# STM32_MACH3-Interfaceboard_V2.net
KiCad netlist of a schematic drawn in EAGLE
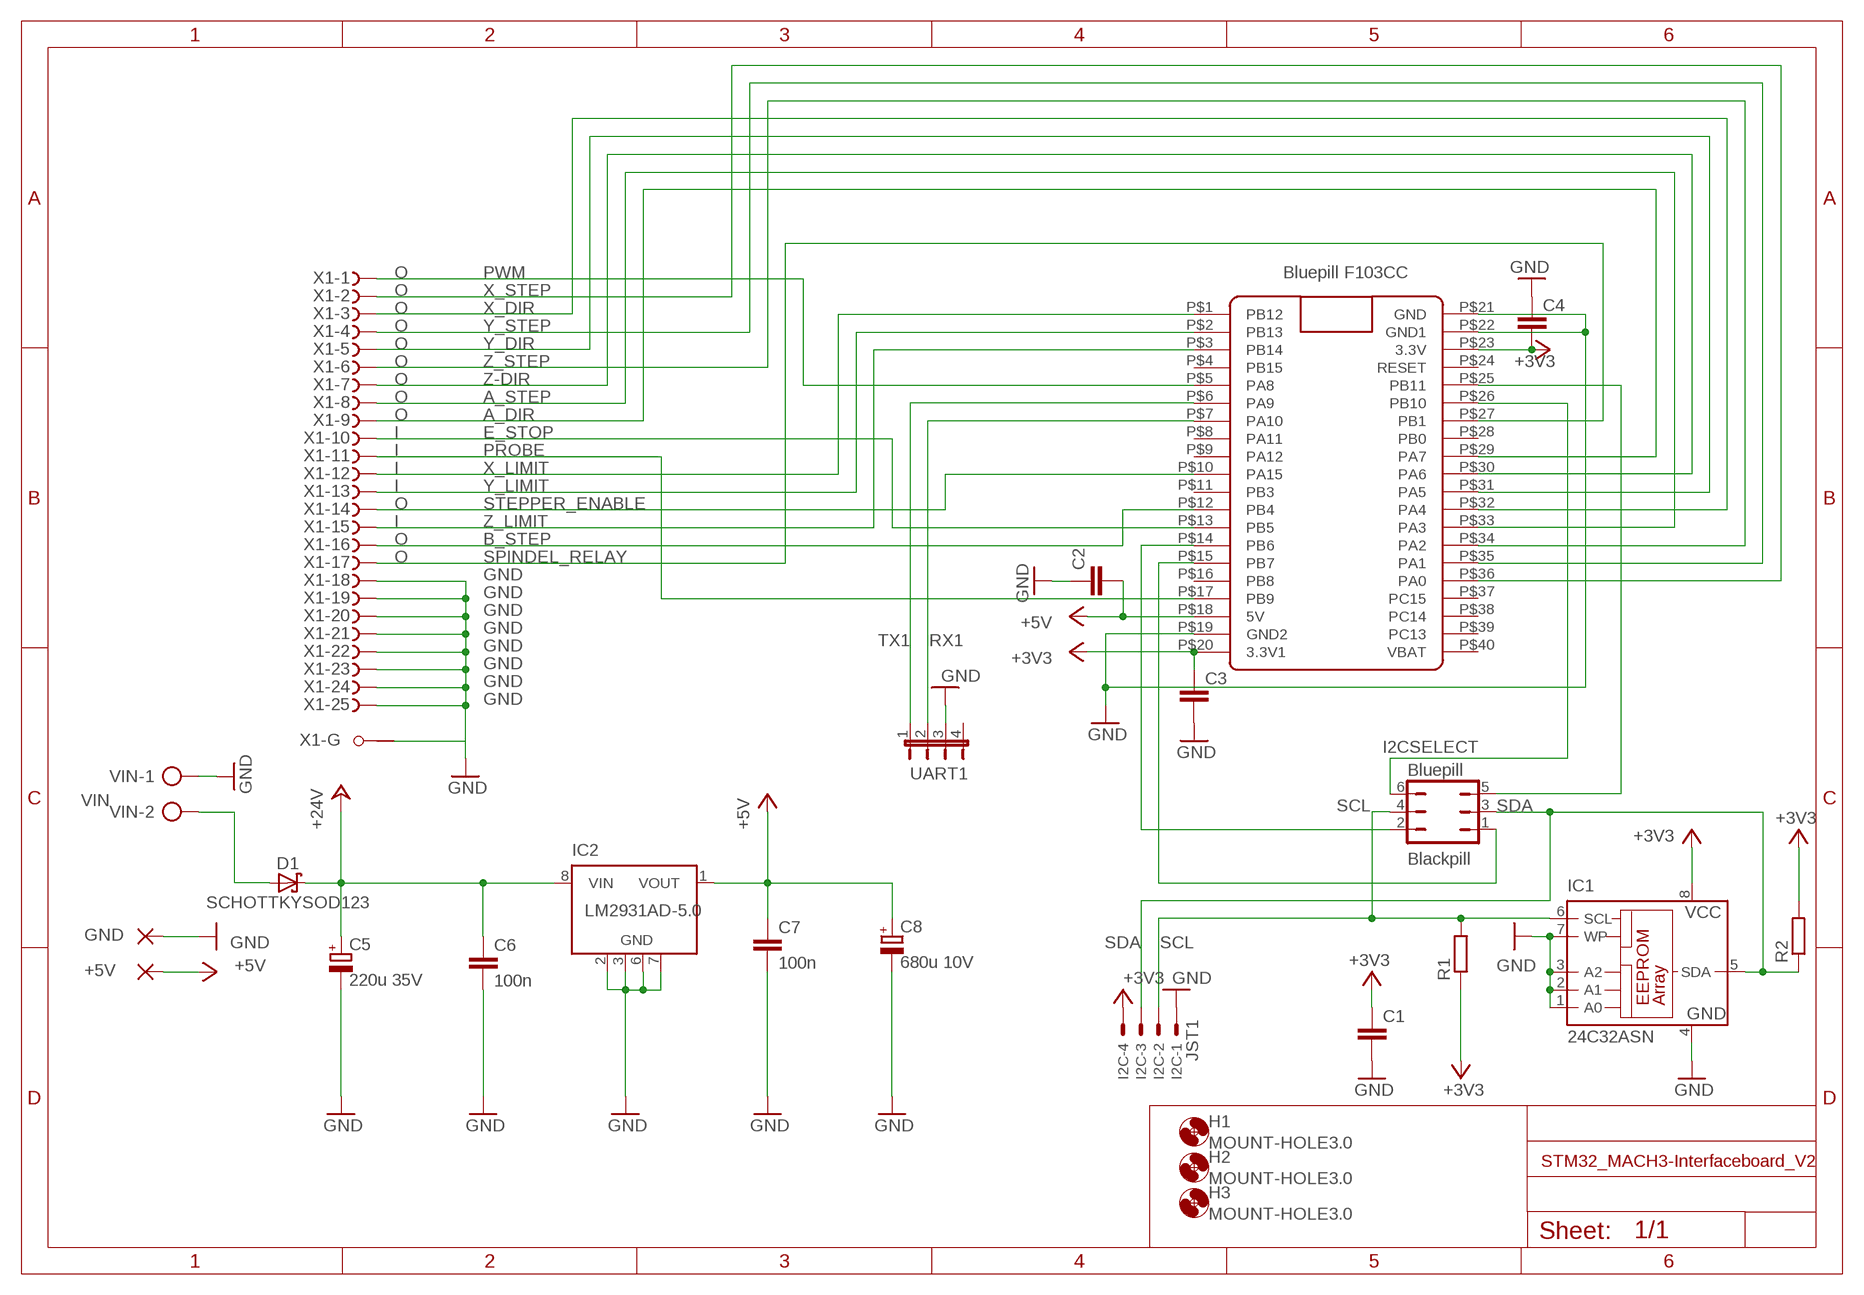
[diagram p0: schematic, sheet 1]

(export (version "E")
  (design (tool "Eeschema 10.0.6"))
  (components
    (comp (ref "+5V")
      (value "2,54/1,0")
      (footprint "eagle-import:2,54_1,0")
      (libsource (lib "eagle-import") (part "2,54/1,0"))
    )
    (comp (ref "C1")
      (value "C-EUC0805")
      (footprint "eagle-import:C0805")
      (libsource (lib "eagle-import") (part "C-EUC0805"))
    )
    (comp (ref "C2")
      (value "C-EUC0805")
      (footprint "eagle-import:C0805")
      (libsource (lib "eagle-import") (part "C-EUC0805"))
    )
    (comp (ref "C3")
      (value "C-EUC0805")
      (footprint "eagle-import:C0805")
      (libsource (lib "eagle-import") (part "C-EUC0805"))
    )
    (comp (ref "C4")
      (value "C-EUC0805")
      (footprint "eagle-import:C0805")
      (libsource (lib "eagle-import") (part "C-EUC0805"))
    )
    (comp (ref "C5")
      (value "220u 35V")
      (footprint "eagle-import:PANASONIC_E7")
      (libsource (lib "eagle-import") (part "C_POLARIZEDE7"))
    )
    (comp (ref "C6")
      (value "100n")
      (footprint "eagle-import:C0805")
      (libsource (lib "eagle-import") (part "CC0805"))
    )
    (comp (ref "C7")
      (value "100n")
      (footprint "eagle-import:C0805")
      (libsource (lib "eagle-import") (part "CC0805"))
    )
    (comp (ref "C8")
      (value "680u 10V")
      (footprint "eagle-import:PANASONIC_E7")
      (libsource (lib "eagle-import") (part "C_POLARIZEDE7"))
    )
    (comp (ref "D1")
      (value "SCHOTTKYSOD123")
      (footprint "eagle-import:SOD123")
      (libsource (lib "eagle-import") (part "SCHOTTKYSOD123"))
    )
    (comp (ref "GND")
      (value "2,54/1,0")
      (footprint "eagle-import:2,54_1,0")
      (libsource (lib "eagle-import") (part "2,54/1,0"))
    )
    (comp (ref "H1")
      (value "MOUNT-HOLE3.0")
      (footprint "eagle-import:3,0")
      (libsource (lib "eagle-import") (part "MOUNT-HOLE3.0"))
    )
    (comp (ref "H2")
      (value "MOUNT-HOLE3.0")
      (footprint "eagle-import:3,0")
      (libsource (lib "eagle-import") (part "MOUNT-HOLE3.0"))
    )
    (comp (ref "H3")
      (value "MOUNT-HOLE3.0")
      (footprint "eagle-import:3,0")
      (libsource (lib "eagle-import") (part "MOUNT-HOLE3.0"))
    )
    (comp (ref "I2C")
      (value "JST1")
      (footprint "eagle-import:JST-XH-04-PACKAGE-LONG-PAD")
      (libsource (lib "eagle-import") (part "JST-XH-04-PIN-LONG-PAD"))
    )
    (comp (ref "I2CSELECT")
      (value "JP3Q")
      (footprint "eagle-import:JP3Q")
      (libsource (lib "eagle-import") (part "JP3Q"))
    )
    (comp (ref "IC1")
      (value "24C32ASN")
      (footprint "eagle-import:SO-08")
      (fields (field (name "MPN") "IS24C32A-2GLI"))
      (libsource (lib "eagle-import") (part "24SNC32A"))
    )
    (comp (ref "IC2")
      (value "LM2931AD-5.0")
      (footprint "eagle-import:SOIC8")
      (libsource (lib "eagle-import") (part "LM2931AD-5.0"))
    )
    (comp (ref "R1")
      (value "R-EU_R0805")
      (footprint "eagle-import:R0805")
      (libsource (lib "eagle-import") (part "R-EU_R0805"))
    )
    (comp (ref "R2")
      (value "R-EU_R0805")
      (footprint "eagle-import:R0805")
      (libsource (lib "eagle-import") (part "R-EU_R0805"))
    )
    (comp (ref "U$1")
      (value "BLUE_PILL")
      (footprint "eagle-import:BLUE_PILL")
      (libsource (lib "eagle-import") (part "BLUE_PILL"))
    )
    (comp (ref "UART1")
      (value "JP4E")
      (footprint "eagle-import:JP4")
      (libsource (lib "eagle-import") (part "JP4E"))
    )
    (comp (ref "VIN")
      (value "AK500/2")
      (footprint "eagle-import:AK500_2")
      (libsource (lib "eagle-import") (part "AK500/2"))
    )
    (comp (ref "X1")
      (value "F25HPS")
      (footprint "eagle-import:F25HP")
      (libsource (lib "eagle-import") (part "F25HPS"))
    )
  )
  (nets
    (net (code "1") (name "+3V3") (class "Default")
      (node (ref "C1") (pin "1") (pinfunction "1_1") (pintype "passive"))
      (node (ref "C3") (pin "1") (pinfunction "1_1") (pintype "passive"))
      (node (ref "C4") (pin "2") (pinfunction "2_2") (pintype "passive"))
      (node (ref "I2C") (pin "4") (pinfunction "S_4") (pintype "passive"))
      (node (ref "IC1") (pin "8") (pinfunction "VCC_8") (pintype "power_in"))
      (node (ref "R1") (pin "1") (pinfunction "1_1") (pintype "passive"))
      (node (ref "R2") (pin "2") (pinfunction "2_2") (pintype "passive"))
      (node (ref "U$1") (pin "P$20") (pinfunction "3.3V1_P$20") (pintype "bidirectional"))
      (node (ref "U$1") (pin "P$23") (pinfunction "3.3V_P$23") (pintype "bidirectional"))
    )
    (net (code "2") (name "+5V") (class "Default")
      (node (ref "+5V") (pin "1") (pinfunction "P_1") (pintype "passive"))
      (node (ref "C2") (pin "2") (pinfunction "2_2") (pintype "passive"))
      (node (ref "C7") (pin "1") (pinfunction "1_1") (pintype "passive"))
      (node (ref "C8") (pin "+") (pinfunction "+_+") (pintype "passive"))
      (node (ref "IC2") (pin "1") (pinfunction "VOUT_1") (pintype "output"))
      (node (ref "U$1") (pin "P$18") (pinfunction "5V_P$18") (pintype "bidirectional"))
    )
    (net (code "3") (name "+24V") (class "Default")
      (node (ref "C5") (pin "+") (pinfunction "+_+") (pintype "passive"))
      (node (ref "C6") (pin "1") (pinfunction "1_1") (pintype "passive"))
      (node (ref "D1") (pin "C") (pinfunction "C_C") (pintype "passive"))
      (node (ref "IC2") (pin "8") (pinfunction "VIN_8") (pintype "passive"))
    )
    (net (code "4") (name "/A_DIR") (class "Default")
      (node (ref "U$1") (pin "P$29") (pinfunction "PA7_P$29") (pintype "bidirectional"))
      (node (ref "X1") (pin "9") (pinfunction "F_9") (pintype "passive"))
    )
    (net (code "5") (name "/A_STEP") (class "Default")
      (node (ref "U$1") (pin "P$33") (pinfunction "PA3_P$33") (pintype "bidirectional"))
      (node (ref "X1") (pin "8") (pinfunction "F_8") (pintype "passive"))
    )
    (net (code "6") (name "/B_STEP") (class "Default")
      (node (ref "U$1") (pin "P$12") (pinfunction "PB4_P$12") (pintype "bidirectional"))
      (node (ref "X1") (pin "16") (pinfunction "F_16") (pintype "passive"))
    )
    (net (code "7") (name "/E_STOP") (class "Default")
      (node (ref "U$1") (pin "P$13") (pinfunction "PB5_P$13") (pintype "bidirectional"))
      (node (ref "X1") (pin "10") (pinfunction "F_10") (pintype "passive"))
    )
    (net (code "8") (name "/PROBE") (class "Default")
      (node (ref "U$1") (pin "P$17") (pinfunction "PB9_P$17") (pintype "bidirectional"))
      (node (ref "X1") (pin "11") (pinfunction "F_11") (pintype "passive"))
    )
    (net (code "9") (name "/PWM") (class "Default")
      (node (ref "U$1") (pin "P$5") (pinfunction "PA8_P$5") (pintype "bidirectional"))
      (node (ref "X1") (pin "1") (pinfunction "F_1") (pintype "passive"))
    )
    (net (code "10") (name "/RX1") (class "Default")
      (node (ref "U$1") (pin "P$7") (pinfunction "PA10_P$7") (pintype "bidirectional"))
      (node (ref "UART1") (pin "2") (pinfunction "2_2") (pintype "passive"))
    )
    (net (code "11") (name "/SCL") (class "Default")
      (node (ref "I2C") (pin "2") (pinfunction "S_2") (pintype "passive"))
      (node (ref "I2CSELECT") (pin "4") (pinfunction "4_4") (pintype "passive"))
      (node (ref "IC1") (pin "6") (pinfunction "SCL_6") (pintype "input"))
      (node (ref "R1") (pin "2") (pinfunction "2_2") (pintype "passive"))
    )
    (net (code "12") (name "/SDA") (class "Default")
      (node (ref "I2C") (pin "3") (pinfunction "S_3") (pintype "passive"))
      (node (ref "I2CSELECT") (pin "3") (pinfunction "3_3") (pintype "passive"))
      (node (ref "IC1") (pin "5") (pinfunction "SDA_5") (pintype "bidirectional"))
      (node (ref "R2") (pin "1") (pinfunction "1_1") (pintype "passive"))
    )
    (net (code "13") (name "/SPINDEL_RELAY") (class "Default")
      (node (ref "U$1") (pin "P$27") (pinfunction "PB1_P$27") (pintype "bidirectional"))
      (node (ref "X1") (pin "17") (pinfunction "F_17") (pintype "passive"))
    )
    (net (code "14") (name "/STEPPER_ENABLE") (class "Default")
      (node (ref "U$1") (pin "P$10") (pinfunction "PA15_P$10") (pintype "bidirectional"))
      (node (ref "X1") (pin "14") (pinfunction "F_14") (pintype "passive"))
    )
    (net (code "15") (name "/TX1") (class "Default")
      (node (ref "U$1") (pin "P$6") (pinfunction "PA9_P$6") (pintype "bidirectional"))
      (node (ref "UART1") (pin "1") (pinfunction "1_1") (pintype "passive"))
    )
    (net (code "16") (name "/VIN") (class "Default")
      (node (ref "D1") (pin "A") (pinfunction "A_A") (pintype "passive"))
      (node (ref "VIN") (pin "2") (pinfunction "KL_2") (pintype "passive"))
    )
    (net (code "17") (name "/X_DIR") (class "Default")
      (node (ref "U$1") (pin "P$32") (pinfunction "PA4_P$32") (pintype "bidirectional"))
      (node (ref "X1") (pin "3") (pinfunction "F_3") (pintype "passive"))
    )
    (net (code "18") (name "/X_LIMIT") (class "Default")
      (node (ref "U$1") (pin "P$1") (pinfunction "PB12_P$1") (pintype "bidirectional"))
      (node (ref "X1") (pin "12") (pinfunction "F_12") (pintype "passive"))
    )
    (net (code "19") (name "/X_STEP") (class "Default")
      (node (ref "U$1") (pin "P$36") (pinfunction "PA0_P$36") (pintype "bidirectional"))
      (node (ref "X1") (pin "2") (pinfunction "F_2") (pintype "passive"))
    )
    (net (code "20") (name "/Y_DIR") (class "Default")
      (node (ref "U$1") (pin "P$31") (pinfunction "PA5_P$31") (pintype "bidirectional"))
      (node (ref "X1") (pin "5") (pinfunction "F_5") (pintype "passive"))
    )
    (net (code "21") (name "/Y_LIMIT") (class "Default")
      (node (ref "U$1") (pin "P$2") (pinfunction "PB13_P$2") (pintype "bidirectional"))
      (node (ref "X1") (pin "13") (pinfunction "F_13") (pintype "passive"))
    )
    (net (code "22") (name "/Y_STEP") (class "Default")
      (node (ref "U$1") (pin "P$35") (pinfunction "PA1_P$35") (pintype "bidirectional"))
      (node (ref "X1") (pin "4") (pinfunction "F_4") (pintype "passive"))
    )
    (net (code "23") (name "/Z-DIR") (class "Default")
      (node (ref "U$1") (pin "P$30") (pinfunction "PA6_P$30") (pintype "bidirectional"))
      (node (ref "X1") (pin "7") (pinfunction "F_7") (pintype "passive"))
    )
    (net (code "24") (name "/Z_LIMIT") (class "Default")
      (node (ref "U$1") (pin "P$3") (pinfunction "PB14_P$3") (pintype "bidirectional"))
      (node (ref "X1") (pin "15") (pinfunction "F_15") (pintype "passive"))
    )
    (net (code "25") (name "/Z_STEP") (class "Default")
      (node (ref "U$1") (pin "P$34") (pinfunction "PA2_P$34") (pintype "bidirectional"))
      (node (ref "X1") (pin "6") (pinfunction "F_6") (pintype "passive"))
    )
    (net (code "26") (name "GND") (class "Default")
      (node (ref "C1") (pin "2") (pinfunction "2_2") (pintype "passive"))
      (node (ref "C2") (pin "1") (pinfunction "1_1") (pintype "passive"))
      (node (ref "C3") (pin "2") (pinfunction "2_2") (pintype "passive"))
      (node (ref "C4") (pin "1") (pinfunction "1_1") (pintype "passive"))
      (node (ref "C5") (pin "-") (pinfunction "-_-") (pintype "passive"))
      (node (ref "C6") (pin "2") (pinfunction "2_2") (pintype "passive"))
      (node (ref "C7") (pin "2") (pinfunction "2_2") (pintype "passive"))
      (node (ref "C8") (pin "-") (pinfunction "-_-") (pintype "passive"))
      (node (ref "GND") (pin "1") (pinfunction "P_1") (pintype "passive"))
      (node (ref "I2C") (pin "1") (pinfunction "S_1") (pintype "passive"))
      (node (ref "IC1") (pin "1") (pinfunction "A0_1") (pintype "input"))
      (node (ref "IC1") (pin "2") (pinfunction "A1_2") (pintype "input"))
      (node (ref "IC1") (pin "3") (pinfunction "A2_3") (pintype "input"))
      (node (ref "IC1") (pin "4") (pinfunction "GND_4") (pintype "power_in"))
      (node (ref "IC1") (pin "7") (pinfunction "WP_7") (pintype "input"))
      (node (ref "IC2") (pin "2") (pinfunction "GND_2") (pintype "power_in"))
      (node (ref "IC2") (pin "3") (pinfunction "GND_3") (pintype "power_in"))
      (node (ref "IC2") (pin "6") (pinfunction "GND_6") (pintype "power_in"))
      (node (ref "IC2") (pin "7") (pinfunction "GND_7") (pintype "power_in"))
      (node (ref "U$1") (pin "P$19") (pinfunction "GND2_P$19") (pintype "bidirectional"))
      (node (ref "U$1") (pin "P$21") (pinfunction "GND_P$21") (pintype "power_in"))
      (node (ref "U$1") (pin "P$22") (pinfunction "GND1_P$22") (pintype "bidirectional"))
      (node (ref "UART1") (pin "3") (pinfunction "3_3") (pintype "passive"))
      (node (ref "VIN") (pin "1") (pinfunction "KL_1") (pintype "passive"))
      (node (ref "X1") (pin "18") (pinfunction "F_18") (pintype "passive"))
      (node (ref "X1") (pin "19") (pinfunction "F_19") (pintype "passive"))
      (node (ref "X1") (pin "20") (pinfunction "F_20") (pintype "passive"))
      (node (ref "X1") (pin "21") (pinfunction "F_21") (pintype "passive"))
      (node (ref "X1") (pin "22") (pinfunction "F_22") (pintype "passive"))
      (node (ref "X1") (pin "23") (pinfunction "F_23") (pintype "passive"))
      (node (ref "X1") (pin "24") (pinfunction "F_24") (pintype "passive"))
      (node (ref "X1") (pin "25") (pinfunction "F_25") (pintype "passive"))
      (node (ref "X1") (pin "G1") (pinfunction "G1_G1") (pintype "passive"))
    )
    (net (code "27") (name "Net-(U$1-PB6)") (class "Default")
      (node (ref "I2CSELECT") (pin "2") (pinfunction "2_2") (pintype "passive"))
      (node (ref "U$1") (pin "P$14") (pinfunction "PB6_P$14") (pintype "bidirectional"))
    )
    (net (code "28") (name "Net-(U$1-PB7)") (class "Default")
      (node (ref "I2CSELECT") (pin "1") (pinfunction "1_1") (pintype "passive"))
      (node (ref "U$1") (pin "P$15") (pinfunction "PB7_P$15") (pintype "bidirectional"))
    )
    (net (code "29") (name "Net-(U$1-PB10)") (class "Default")
      (node (ref "I2CSELECT") (pin "6") (pinfunction "6_6") (pintype "passive"))
      (node (ref "U$1") (pin "P$26") (pinfunction "PB10_P$26") (pintype "bidirectional"))
    )
    (net (code "30") (name "Net-(U$1-PB11)") (class "Default")
      (node (ref "I2CSELECT") (pin "5") (pinfunction "5_5") (pintype "passive"))
      (node (ref "U$1") (pin "P$25") (pinfunction "PB11_P$25") (pintype "bidirectional"))
    )
    (net (code "31") (name "unconnected-(U$1-PA11-PadP$8)") (class "Default")
      (node (ref "U$1") (pin "P$8") (pinfunction "PA11_P$8") (pintype "bidirectional"))
    )
    (net (code "32") (name "unconnected-(U$1-PA12-PadP$9)") (class "Default")
      (node (ref "U$1") (pin "P$9") (pinfunction "PA12_P$9") (pintype "bidirectional"))
    )
    (net (code "33") (name "unconnected-(U$1-PB0-PadP$28)") (class "Default")
      (node (ref "U$1") (pin "P$28") (pinfunction "PB0_P$28") (pintype "bidirectional"))
    )
    (net (code "34") (name "unconnected-(U$1-PB3-PadP$11)") (class "Default")
      (node (ref "U$1") (pin "P$11") (pinfunction "PB3_P$11") (pintype "bidirectional"))
    )
    (net (code "35") (name "unconnected-(U$1-PB8-PadP$16)") (class "Default")
      (node (ref "U$1") (pin "P$16") (pinfunction "PB8_P$16") (pintype "bidirectional"))
    )
    (net (code "36") (name "unconnected-(U$1-PB15-PadP$4)") (class "Default")
      (node (ref "U$1") (pin "P$4") (pinfunction "PB15_P$4") (pintype "bidirectional"))
    )
    (net (code "37") (name "unconnected-(U$1-PC13-PadP$39)") (class "Default")
      (node (ref "U$1") (pin "P$39") (pinfunction "PC13_P$39") (pintype "bidirectional"))
    )
    (net (code "38") (name "unconnected-(U$1-PC14-PadP$38)") (class "Default")
      (node (ref "U$1") (pin "P$38") (pinfunction "PC14_P$38") (pintype "bidirectional"))
    )
    (net (code "39") (name "unconnected-(U$1-PC15-PadP$37)") (class "Default")
      (node (ref "U$1") (pin "P$37") (pinfunction "PC15_P$37") (pintype "bidirectional"))
    )
    (net (code "40") (name "unconnected-(U$1-RESET-PadP$24)") (class "Default")
      (node (ref "U$1") (pin "P$24") (pinfunction "RESET_P$24") (pintype "bidirectional"))
    )
    (net (code "41") (name "unconnected-(U$1-VBAT-PadP$40)") (class "Default")
      (node (ref "U$1") (pin "P$40") (pinfunction "VBAT_P$40") (pintype "bidirectional"))
    )
    (net (code "42") (name "unconnected-(UART1-Pad4)") (class "Default")
      (node (ref "UART1") (pin "4") (pinfunction "4_4") (pintype "passive"))
    )
    (net (code "43") (name "unconnected-(X1-PadG2)") (class "Default")
      (node (ref "X1") (pin "G2") (pinfunction "G2_G2") (pintype "passive"))
    )
  )
)
